# BMS_AFE_-_Connectors.net
KiCad netlist of a schematic drawn in Altium Designer
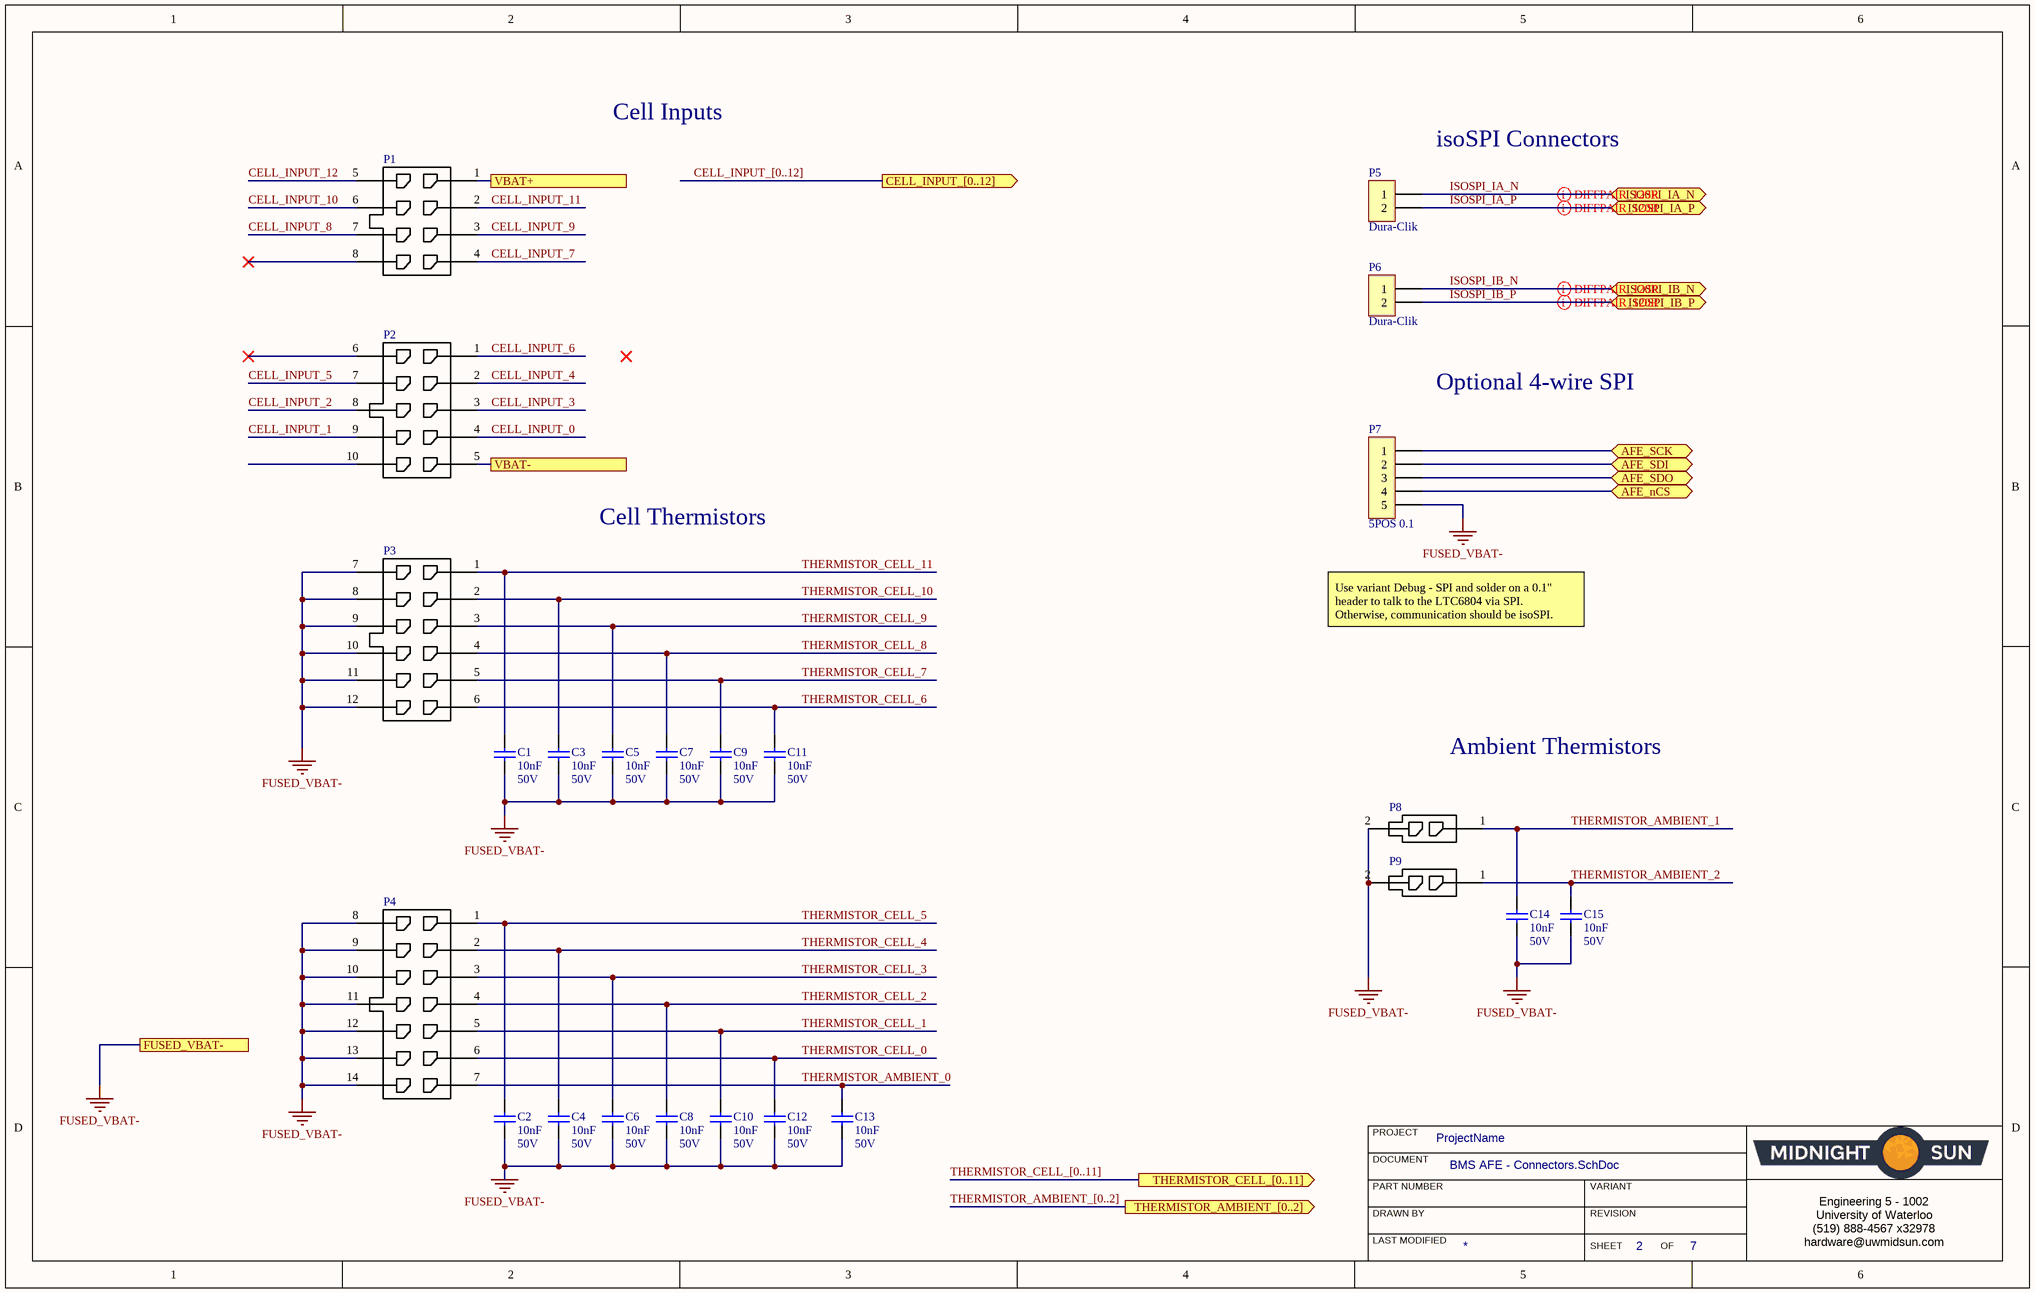
[diagram p0: BMS AFE - Connectors.SchDoc]

(export (version "E")
  (design (tool "Eeschema 10.0.6"))
  (components
    (comp (ref "C1")
      (value "CAP CER 10nF 50V 5% X7R 0603")
      (footprint "CAP, 0603")
      (description "10000pF ±5% 50V Ceramic Capacitor U2J 0603 (1608 Metric)")
      (fields
        (field (name "TOLERANCE") "±5%")
        (field (name "CAPACITANCE") "10nF")
        (field (name "VOLTAGE") "50V")
      )
      (libsource (lib "Schematic Diagrams") (part "CAP CER 10nF 50V 5% X7R 0603"))
    )
    (comp (ref "C2")
      (value "CAP CER 10nF 50V 5% X7R 0603")
      (footprint "CAP, 0603")
      (description "10000pF ±5% 50V Ceramic Capacitor U2J 0603 (1608 Metric)")
      (fields
        (field (name "TOLERANCE") "±5%")
        (field (name "CAPACITANCE") "10nF")
        (field (name "VOLTAGE") "50V")
      )
      (libsource (lib "Schematic Diagrams") (part "CAP CER 10nF 50V 5% X7R 0603"))
    )
    (comp (ref "C3")
      (value "CAP CER 10nF 50V 5% X7R 0603")
      (footprint "CAP, 0603")
      (description "10000pF ±5% 50V Ceramic Capacitor U2J 0603 (1608 Metric)")
      (fields
        (field (name "TOLERANCE") "±5%")
        (field (name "CAPACITANCE") "10nF")
        (field (name "VOLTAGE") "50V")
      )
      (libsource (lib "Schematic Diagrams") (part "CAP CER 10nF 50V 5% X7R 0603"))
    )
    (comp (ref "C4")
      (value "CAP CER 10nF 50V 5% X7R 0603")
      (footprint "CAP, 0603")
      (description "10000pF ±5% 50V Ceramic Capacitor U2J 0603 (1608 Metric)")
      (fields
        (field (name "TOLERANCE") "±5%")
        (field (name "CAPACITANCE") "10nF")
        (field (name "VOLTAGE") "50V")
      )
      (libsource (lib "Schematic Diagrams") (part "CAP CER 10nF 50V 5% X7R 0603"))
    )
    (comp (ref "C5")
      (value "CAP CER 10nF 50V 5% X7R 0603")
      (footprint "CAP, 0603")
      (description "10000pF ±5% 50V Ceramic Capacitor U2J 0603 (1608 Metric)")
      (fields
        (field (name "TOLERANCE") "±5%")
        (field (name "CAPACITANCE") "10nF")
        (field (name "VOLTAGE") "50V")
      )
      (libsource (lib "Schematic Diagrams") (part "CAP CER 10nF 50V 5% X7R 0603"))
    )
    (comp (ref "C6")
      (value "CAP CER 10nF 50V 5% X7R 0603")
      (footprint "CAP, 0603")
      (description "10000pF ±5% 50V Ceramic Capacitor U2J 0603 (1608 Metric)")
      (fields
        (field (name "TOLERANCE") "±5%")
        (field (name "CAPACITANCE") "10nF")
        (field (name "VOLTAGE") "50V")
      )
      (libsource (lib "Schematic Diagrams") (part "CAP CER 10nF 50V 5% X7R 0603"))
    )
    (comp (ref "C7")
      (value "CAP CER 10nF 50V 5% X7R 0603")
      (footprint "CAP, 0603")
      (description "10000pF ±5% 50V Ceramic Capacitor U2J 0603 (1608 Metric)")
      (fields
        (field (name "TOLERANCE") "±5%")
        (field (name "CAPACITANCE") "10nF")
        (field (name "VOLTAGE") "50V")
      )
      (libsource (lib "Schematic Diagrams") (part "CAP CER 10nF 50V 5% X7R 0603"))
    )
    (comp (ref "C8")
      (value "CAP CER 10nF 50V 5% X7R 0603")
      (footprint "CAP, 0603")
      (description "10000pF ±5% 50V Ceramic Capacitor U2J 0603 (1608 Metric)")
      (fields
        (field (name "TOLERANCE") "±5%")
        (field (name "CAPACITANCE") "10nF")
        (field (name "VOLTAGE") "50V")
      )
      (libsource (lib "Schematic Diagrams") (part "CAP CER 10nF 50V 5% X7R 0603"))
    )
    (comp (ref "C9")
      (value "CAP CER 10nF 50V 5% X7R 0603")
      (footprint "CAP, 0603")
      (description "10000pF ±5% 50V Ceramic Capacitor U2J 0603 (1608 Metric)")
      (fields
        (field (name "TOLERANCE") "±5%")
        (field (name "CAPACITANCE") "10nF")
        (field (name "VOLTAGE") "50V")
      )
      (libsource (lib "Schematic Diagrams") (part "CAP CER 10nF 50V 5% X7R 0603"))
    )
    (comp (ref "C10")
      (value "CAP CER 10nF 50V 5% X7R 0603")
      (footprint "CAP, 0603")
      (description "10000pF ±5% 50V Ceramic Capacitor U2J 0603 (1608 Metric)")
      (fields
        (field (name "TOLERANCE") "±5%")
        (field (name "CAPACITANCE") "10nF")
        (field (name "VOLTAGE") "50V")
      )
      (libsource (lib "Schematic Diagrams") (part "CAP CER 10nF 50V 5% X7R 0603"))
    )
    (comp (ref "C11")
      (value "CAP CER 10nF 50V 5% X7R 0603")
      (footprint "CAP, 0603")
      (description "10000pF ±5% 50V Ceramic Capacitor U2J 0603 (1608 Metric)")
      (fields
        (field (name "TOLERANCE") "±5%")
        (field (name "CAPACITANCE") "10nF")
        (field (name "VOLTAGE") "50V")
      )
      (libsource (lib "Schematic Diagrams") (part "CAP CER 10nF 50V 5% X7R 0603"))
    )
    (comp (ref "C12")
      (value "CAP CER 10nF 50V 5% X7R 0603")
      (footprint "CAP, 0603")
      (description "10000pF ±5% 50V Ceramic Capacitor U2J 0603 (1608 Metric)")
      (fields
        (field (name "TOLERANCE") "±5%")
        (field (name "CAPACITANCE") "10nF")
        (field (name "VOLTAGE") "50V")
      )
      (libsource (lib "Schematic Diagrams") (part "CAP CER 10nF 50V 5% X7R 0603"))
    )
    (comp (ref "C13")
      (value "CAP CER 10nF 50V 5% X7R 0603")
      (footprint "CAP, 0603")
      (description "10000pF ±5% 50V Ceramic Capacitor U2J 0603 (1608 Metric)")
      (fields
        (field (name "TOLERANCE") "±5%")
        (field (name "CAPACITANCE") "10nF")
        (field (name "VOLTAGE") "50V")
      )
      (libsource (lib "Schematic Diagrams") (part "CAP CER 10nF 50V 5% X7R 0603"))
    )
    (comp (ref "C14")
      (value "CAP CER 10nF 50V 5% X7R 0603")
      (footprint "CAP, 0603")
      (description "10000pF ±5% 50V Ceramic Capacitor U2J 0603 (1608 Metric)")
      (fields
        (field (name "TOLERANCE") "±5%")
        (field (name "CAPACITANCE") "10nF")
        (field (name "VOLTAGE") "50V")
      )
      (libsource (lib "Schematic Diagrams") (part "CAP CER 10nF 50V 5% X7R 0603"))
    )
    (comp (ref "C15")
      (value "CAP CER 10nF 50V 5% X7R 0603")
      (footprint "CAP, 0603")
      (description "10000pF ±5% 50V Ceramic Capacitor U2J 0603 (1608 Metric)")
      (fields
        (field (name "TOLERANCE") "±5%")
        (field (name "CAPACITANCE") "10nF")
        (field (name "VOLTAGE") "50V")
      )
      (libsource (lib "Schematic Diagrams") (part "CAP CER 10nF 50V 5% X7R 0603"))
    )
    (comp (ref "P1")
      (value "CONN 8POS MICRO-FIT 3mm")
      (description "Connector Header Through Hole 6 position 0.118\" (3.00mm)")
      (fields
        (field (name "MANUFACTURER") "Molex, LLC")
        (field (name "MANUFACTURER PART NUMBER") "0430450827")
      )
      (libsource (lib "Schematic Diagrams") (part "CONN 8POS MICRO-FIT 3mm"))
    )
    (comp (ref "P2")
      (value "CONN 10POS MICRO-FIT 3mm")
      (footprint "CONN, 10POS MICRO-FIT 3mm")
      (description "Connector Header Through Hole 10 position 0.118\" (3.00mm)")
      (fields
        (field (name "MANUFACTURER") "Molex, LLC")
        (field (name "MANUFACTURER PART NUMBER") "0430451027")
      )
      (libsource (lib "Schematic Diagrams") (part "CONN 10POS MICRO-FIT 3mm"))
    )
    (comp (ref "P3")
      (value "CONN 12POS MICRO-FIT 3mm")
      (footprint "CONN, 12POS MICRO-FIT 3mm")
      (description "Connector Header Through Hole 12 position 0.118\" (3.00mm)")
      (fields
        (field (name "MANUFACTURER") "Molex, LLC")
        (field (name "MANUFACTURER PART NUMBER") "0430451227")
      )
      (libsource (lib "Schematic Diagrams") (part "CONN 12POS MICRO-FIT 3mm"))
    )
    (comp (ref "P4")
      (value "CONN 14POS MICRO-FIT 3mm")
      (footprint "CONN, 14POS MICRO-FIT 3mm")
      (description "Connector Header Through Hole 14 position 0.118\" (3.00mm)")
      (fields
        (field (name "MANUFACTURER") "Molex, LLC")
        (field (name "MANUFACTURER PART NUMBER") "0430451427")
      )
      (libsource (lib "Schematic Diagrams") (part "CONN 14POS MICRO-FIT 3mm"))
    )
    (comp (ref "P5")
      (value "Dura-Clik")
      (footprint "CONN, 2POS Dura-Click Vertical")
      (description "2 Positions Header, Shrouded Connector 0.079\" (2.00mm) Surface Mount, Vertical Tin")
      (fields
        (field (name "MANUFACTURER") "Molex, LLC")
        (field (name "MANUFACTURER PART NUMBER") "5600200220")
      )
      (libsource (lib "Schematic Diagrams") (part "CONN 2POS DURA-CLIK 0.079{dblquote} VERT"))
    )
    (comp (ref "P6")
      (value "Dura-Clik")
      (footprint "CONN, 2POS Dura-Click Vertical")
      (description "2 Positions Header, Shrouded Connector 0.079\" (2.00mm) Surface Mount, Vertical Tin")
      (fields
        (field (name "MANUFACTURER") "Molex, LLC")
        (field (name "MANUFACTURER PART NUMBER") "5600200220")
      )
      (libsource (lib "Schematic Diagrams") (part "CONN 2POS DURA-CLIK 0.079{dblquote} VERT"))
    )
    (comp (ref "P7")
      (value "5POS 0.1")
      (footprint "CONN, 5POS HEADR 0.1\"")
      (description "5 Positions Header, Breakaway Connector 0.100\" (2.54mm) Through Hole Tin")
      (libsource (lib "Schematic Diagrams") (part "CONN 5POS HEADR MALE 0.1in"))
    )
    (comp (ref "P8")
      (value "CONN 2POS MICRO-FIT 3mm")
      (footprint "CONN, 2POS MICRO-FIT")
      (description "Connector Header Through Hole 2 position")
      (fields (field (name "MANUFACTURER") "Molex") (field (name "MANUFACTURER PART NUMBER") "43045-0227"))
      (libsource (lib "Schematic Diagrams") (part "CONN 2POS MICRO-FIT 3mm"))
    )
    (comp (ref "P9")
      (value "CONN 2POS MICRO-FIT 3mm")
      (footprint "CONN, 2POS MICRO-FIT")
      (description "Connector Header Through Hole 2 position")
      (fields (field (name "MANUFACTURER") "Molex") (field (name "MANUFACTURER PART NUMBER") "43045-0227"))
      (libsource (lib "Schematic Diagrams") (part "CONN 2POS MICRO-FIT 3mm"))
    )
  )
  (nets
    (net (code "1") (name "/AFE_SCK") (class "Default")
      (node (ref "P7") (pin "1") (pinfunction "1_1") (pintype "passive"))
    )
    (net (code "2") (name "/AFE_SDI") (class "Default")
      (node (ref "P7") (pin "2") (pinfunction "2_2") (pintype "passive"))
    )
    (net (code "3") (name "/AFE_SDO") (class "Default")
      (node (ref "P7") (pin "3") (pinfunction "3_3") (pintype "passive"))
    )
    (net (code "4") (name "/AFE_nCS") (class "Default")
      (node (ref "P7") (pin "4") (pinfunction "4_4") (pintype "passive"))
    )
    (net (code "5") (name "/CELL_INPUT_0") (class "Default")
      (node (ref "P2") (pin "4") (pinfunction "4_4") (pintype "passive"))
    )
    (net (code "6") (name "/CELL_INPUT_1") (class "Default")
      (node (ref "P2") (pin "9") (pinfunction "9_9") (pintype "passive"))
    )
    (net (code "7") (name "/CELL_INPUT_2") (class "Default")
      (node (ref "P2") (pin "8") (pinfunction "8_8") (pintype "passive"))
    )
    (net (code "8") (name "/CELL_INPUT_3") (class "Default")
      (node (ref "P2") (pin "3") (pinfunction "3_3") (pintype "passive"))
    )
    (net (code "9") (name "/CELL_INPUT_4") (class "Default")
      (node (ref "P2") (pin "2") (pinfunction "2_2") (pintype "passive"))
    )
    (net (code "10") (name "/CELL_INPUT_5") (class "Default")
      (node (ref "P2") (pin "7") (pinfunction "7_7") (pintype "passive"))
    )
    (net (code "11") (name "/CELL_INPUT_6") (class "Default")
      (node (ref "P2") (pin "1") (pinfunction "1_1") (pintype "passive"))
    )
    (net (code "12") (name "/CELL_INPUT_7") (class "Default")
      (node (ref "P1") (pin "4") (pinfunction "4_4") (pintype "passive"))
    )
    (net (code "13") (name "/CELL_INPUT_8") (class "Default")
      (node (ref "P1") (pin "7") (pinfunction "7_7") (pintype "passive"))
    )
    (net (code "14") (name "/CELL_INPUT_9") (class "Default")
      (node (ref "P1") (pin "3") (pinfunction "3_3") (pintype "passive"))
    )
    (net (code "15") (name "/CELL_INPUT_10") (class "Default")
      (node (ref "P1") (pin "6") (pinfunction "6_6") (pintype "passive"))
    )
    (net (code "16") (name "/CELL_INPUT_11") (class "Default")
      (node (ref "P1") (pin "2") (pinfunction "2_2") (pintype "passive"))
    )
    (net (code "17") (name "/CELL_INPUT_12") (class "Default")
      (node (ref "P1") (pin "5") (pinfunction "5_5") (pintype "passive"))
    )
    (net (code "19") (name "/ISOSPI_IA_N") (class "Default")
      (node (ref "P5") (pin "1") (pinfunction "1_1") (pintype "passive"))
    )
    (net (code "20") (name "/ISOSPI_IA_P") (class "Default")
      (node (ref "P5") (pin "2") (pinfunction "2_2") (pintype "passive"))
    )
    (net (code "21") (name "/ISOSPI_IB_N") (class "Default")
      (node (ref "P6") (pin "1") (pinfunction "1_1") (pintype "passive"))
    )
    (net (code "22") (name "/ISOSPI_IB_P") (class "Default")
      (node (ref "P6") (pin "2") (pinfunction "2_2") (pintype "passive"))
    )
    (net (code "23") (name "/THERMISTOR_AMBIENT_0") (class "Default")
      (node (ref "C13") (pin "1") (pinfunction "1_1") (pintype "passive"))
      (node (ref "P4") (pin "7") (pinfunction "7_7") (pintype "passive"))
    )
    (net (code "24") (name "/THERMISTOR_AMBIENT_1") (class "Default")
      (node (ref "C14") (pin "1") (pinfunction "1_1") (pintype "passive"))
      (node (ref "P8") (pin "1") (pinfunction "1_1") (pintype "passive"))
    )
    (net (code "25") (name "/THERMISTOR_AMBIENT_2") (class "Default")
      (node (ref "C15") (pin "1") (pinfunction "1_1") (pintype "passive"))
      (node (ref "P9") (pin "1") (pinfunction "1_1") (pintype "passive"))
    )
    (net (code "27") (name "/THERMISTOR_CELL_0") (class "Default")
      (node (ref "C12") (pin "1") (pinfunction "1_1") (pintype "passive"))
      (node (ref "P4") (pin "6") (pinfunction "6_6") (pintype "passive"))
    )
    (net (code "28") (name "/THERMISTOR_CELL_1") (class "Default")
      (node (ref "C10") (pin "1") (pinfunction "1_1") (pintype "passive"))
      (node (ref "P4") (pin "5") (pinfunction "5_5") (pintype "passive"))
    )
    (net (code "29") (name "/THERMISTOR_CELL_2") (class "Default")
      (node (ref "C8") (pin "1") (pinfunction "1_1") (pintype "passive"))
      (node (ref "P4") (pin "4") (pinfunction "4_4") (pintype "passive"))
    )
    (net (code "30") (name "/THERMISTOR_CELL_3") (class "Default")
      (node (ref "C6") (pin "1") (pinfunction "1_1") (pintype "passive"))
      (node (ref "P4") (pin "3") (pinfunction "3_3") (pintype "passive"))
    )
    (net (code "31") (name "/THERMISTOR_CELL_4") (class "Default")
      (node (ref "C4") (pin "1") (pinfunction "1_1") (pintype "passive"))
      (node (ref "P4") (pin "2") (pinfunction "2_2") (pintype "passive"))
    )
    (net (code "32") (name "/THERMISTOR_CELL_5") (class "Default")
      (node (ref "C2") (pin "1") (pinfunction "1_1") (pintype "passive"))
      (node (ref "P4") (pin "1") (pinfunction "1_1") (pintype "passive"))
    )
    (net (code "33") (name "/THERMISTOR_CELL_6") (class "Default")
      (node (ref "C11") (pin "1") (pinfunction "1_1") (pintype "passive"))
      (node (ref "P3") (pin "6") (pinfunction "6_6") (pintype "passive"))
    )
    (net (code "34") (name "/THERMISTOR_CELL_7") (class "Default")
      (node (ref "C9") (pin "1") (pinfunction "1_1") (pintype "passive"))
      (node (ref "P3") (pin "5") (pinfunction "5_5") (pintype "passive"))
    )
    (net (code "35") (name "/THERMISTOR_CELL_8") (class "Default")
      (node (ref "C7") (pin "1") (pinfunction "1_1") (pintype "passive"))
      (node (ref "P3") (pin "4") (pinfunction "4_4") (pintype "passive"))
    )
    (net (code "36") (name "/THERMISTOR_CELL_9") (class "Default")
      (node (ref "C5") (pin "1") (pinfunction "1_1") (pintype "passive"))
      (node (ref "P3") (pin "3") (pinfunction "3_3") (pintype "passive"))
    )
    (net (code "37") (name "/THERMISTOR_CELL_10") (class "Default")
      (node (ref "C3") (pin "1") (pinfunction "1_1") (pintype "passive"))
      (node (ref "P3") (pin "2") (pinfunction "2_2") (pintype "passive"))
    )
    (net (code "38") (name "/THERMISTOR_CELL_11") (class "Default")
      (node (ref "C1") (pin "1") (pinfunction "1_1") (pintype "passive"))
      (node (ref "P3") (pin "1") (pinfunction "1_1") (pintype "passive"))
    )
    (net (code "40") (name "/VBAT+") (class "Default")
      (node (ref "P1") (pin "1") (pinfunction "1_1") (pintype "passive"))
    )
    (net (code "41") (name "/VBAT-") (class "Default")
      (node (ref "P2") (pin "5") (pinfunction "5_5") (pintype "passive"))
    )
    (net (code "42") (name "FUSED_VBAT-") (class "Default")
      (node (ref "C1") (pin "2") (pinfunction "2_2") (pintype "passive"))
      (node (ref "C10") (pin "2") (pinfunction "2_2") (pintype "passive"))
      (node (ref "C11") (pin "2") (pinfunction "2_2") (pintype "passive"))
      (node (ref "C12") (pin "2") (pinfunction "2_2") (pintype "passive"))
      (node (ref "C13") (pin "2") (pinfunction "2_2") (pintype "passive"))
      (node (ref "C14") (pin "2") (pinfunction "2_2") (pintype "passive"))
      (node (ref "C15") (pin "2") (pinfunction "2_2") (pintype "passive"))
      (node (ref "C2") (pin "2") (pinfunction "2_2") (pintype "passive"))
      (node (ref "C3") (pin "2") (pinfunction "2_2") (pintype "passive"))
      (node (ref "C4") (pin "2") (pinfunction "2_2") (pintype "passive"))
      (node (ref "C5") (pin "2") (pinfunction "2_2") (pintype "passive"))
      (node (ref "C6") (pin "2") (pinfunction "2_2") (pintype "passive"))
      (node (ref "C7") (pin "2") (pinfunction "2_2") (pintype "passive"))
      (node (ref "C8") (pin "2") (pinfunction "2_2") (pintype "passive"))
      (node (ref "C9") (pin "2") (pinfunction "2_2") (pintype "passive"))
      (node (ref "P3") (pin "10") (pinfunction "10_10") (pintype "passive"))
      (node (ref "P3") (pin "11") (pinfunction "11_11") (pintype "passive"))
      (node (ref "P3") (pin "12") (pinfunction "12_12") (pintype "passive"))
      (node (ref "P3") (pin "7") (pinfunction "7_7") (pintype "passive"))
      (node (ref "P3") (pin "8") (pinfunction "8_8") (pintype "passive"))
      (node (ref "P3") (pin "9") (pinfunction "9_9") (pintype "passive"))
      (node (ref "P4") (pin "10") (pinfunction "10_10") (pintype "passive"))
      (node (ref "P4") (pin "11") (pinfunction "11_11") (pintype "passive"))
      (node (ref "P4") (pin "12") (pinfunction "12_12") (pintype "passive"))
      (node (ref "P4") (pin "13") (pinfunction "13_13") (pintype "passive"))
      (node (ref "P4") (pin "14") (pinfunction "14_14") (pintype "passive"))
      (node (ref "P4") (pin "8") (pinfunction "8_8") (pintype "passive"))
      (node (ref "P4") (pin "9") (pinfunction "9_9") (pintype "passive"))
      (node (ref "P7") (pin "5") (pinfunction "5_5") (pintype "passive"))
      (node (ref "P8") (pin "2") (pinfunction "2_2") (pintype "passive"))
      (node (ref "P9") (pin "2") (pinfunction "2_2") (pintype "passive"))
    )
    (net (code "43") (name "unconnected-(P1-Pad8)") (class "Default")
      (node (ref "P1") (pin "8") (pinfunction "8_8") (pintype "passive+no_connect"))
    )
    (net (code "44") (name "unconnected-(P2-Pad6)") (class "Default")
      (node (ref "P2") (pin "6") (pinfunction "6_6") (pintype "passive+no_connect"))
    )
    (net (code "45") (name "unconnected-(P2-Pad10)") (class "Default")
      (node (ref "P2") (pin "10") (pinfunction "10_10") (pintype "passive"))
    )
  )
)
